# Core_Board.net
KiCad netlist of a schematic drawn in Altium Designer
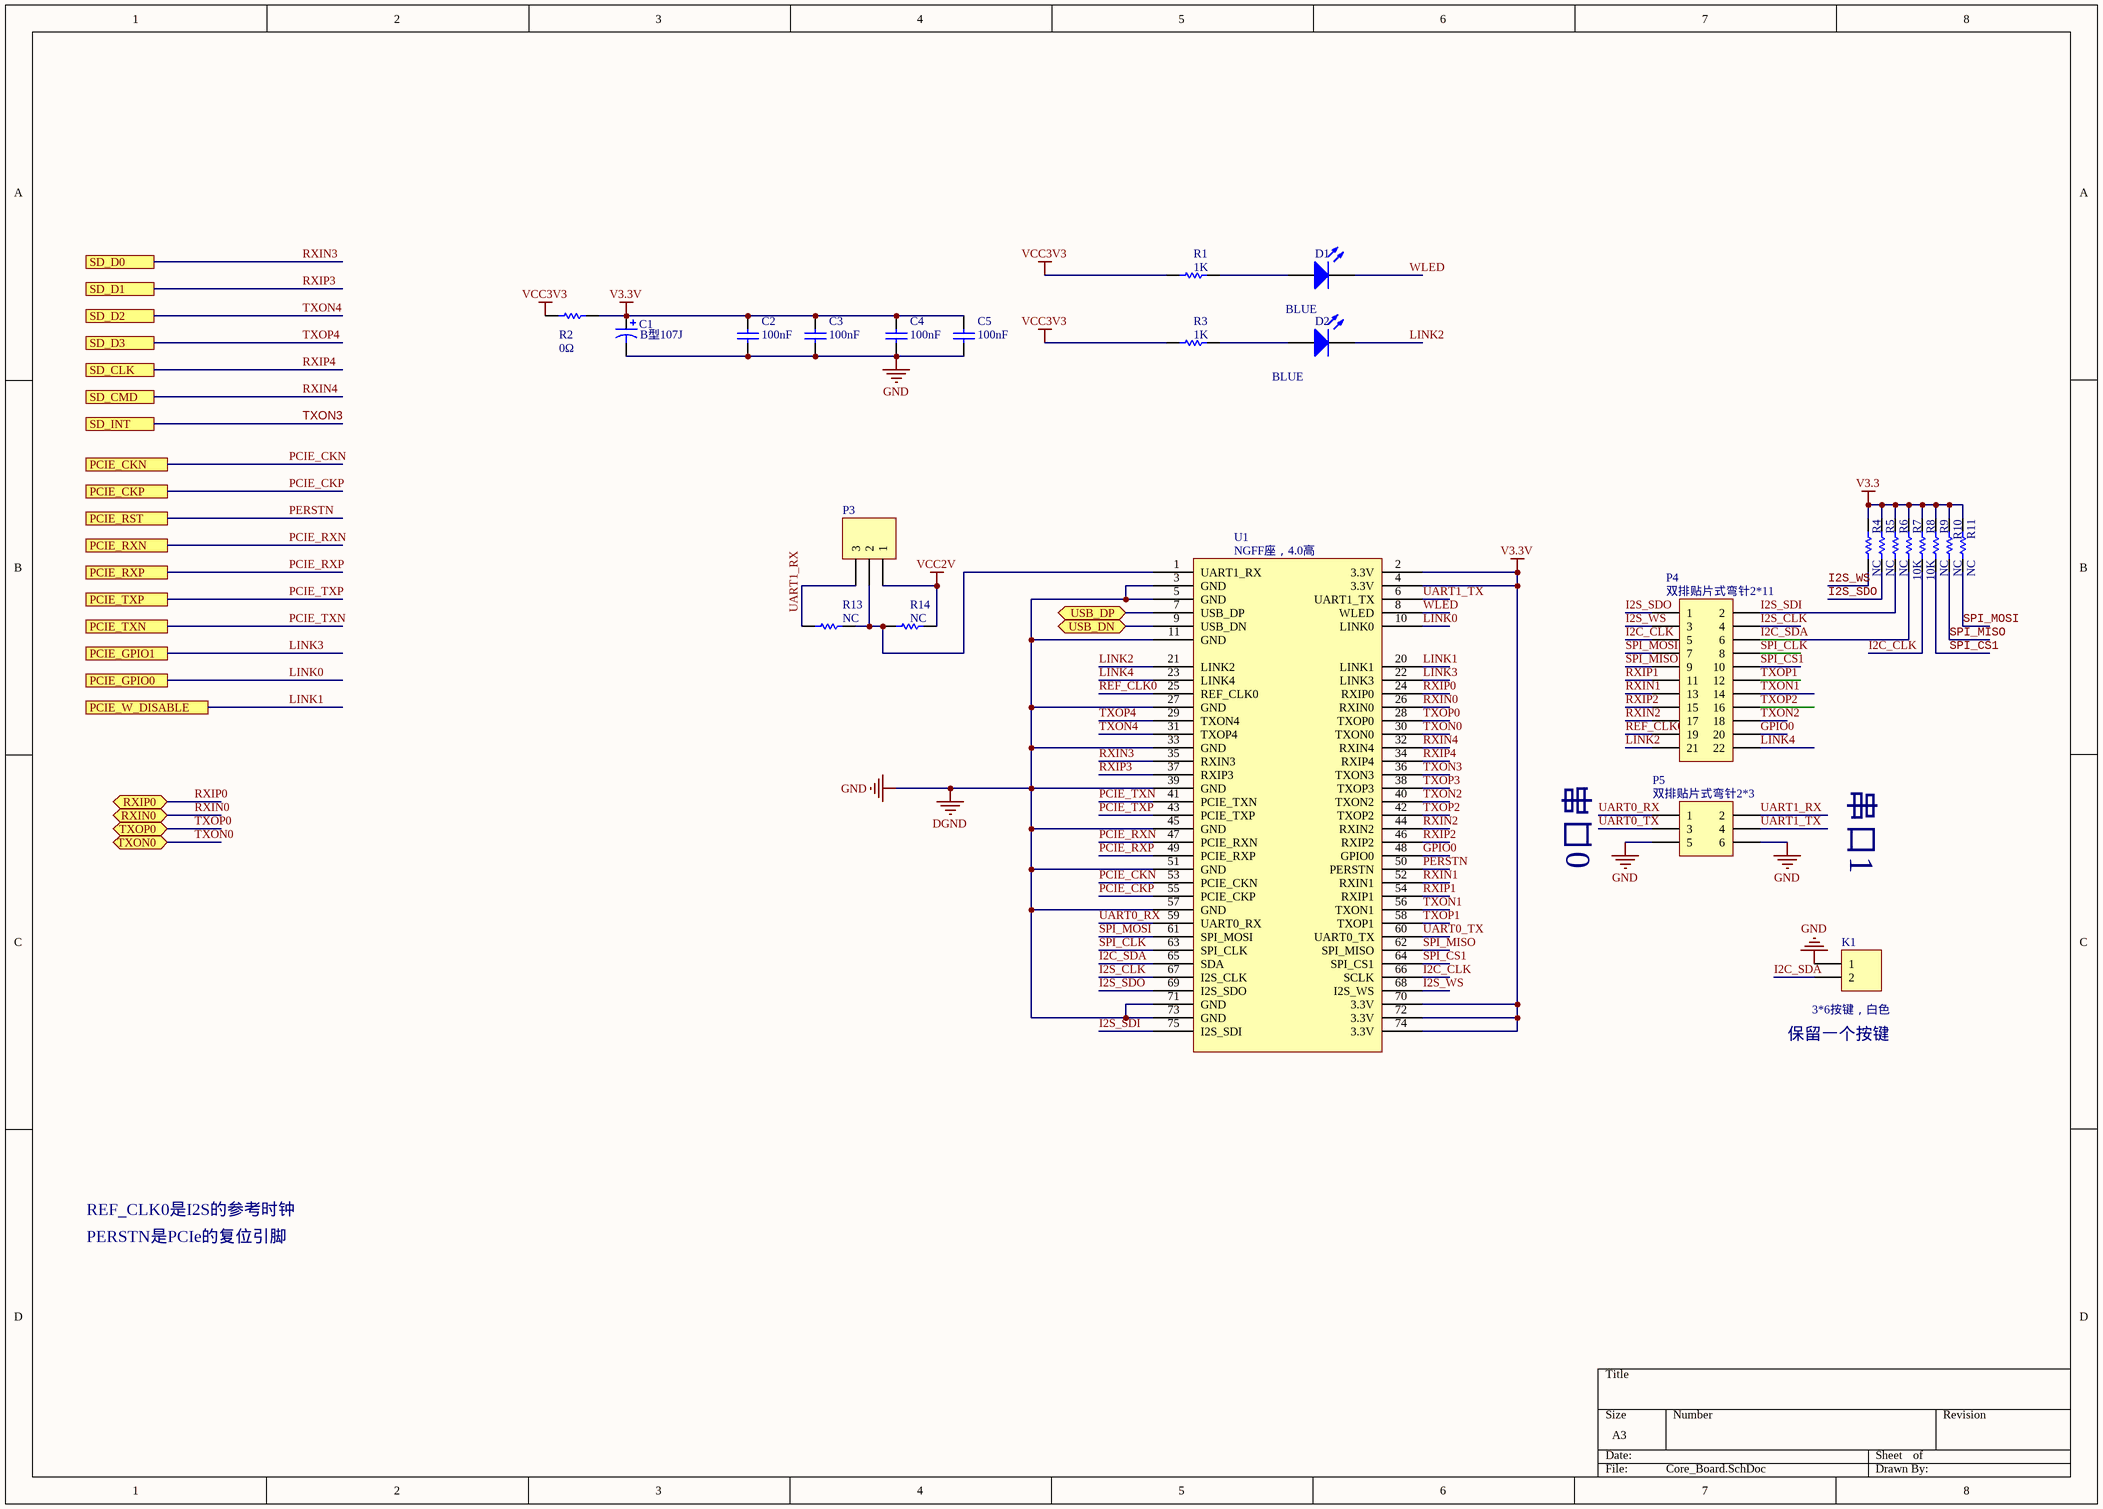
[diagram p0: Core_Board.SchDoc]

(export (version "E")
  (design (tool "Eeschema 10.0.6"))
  (components
    (comp (ref "C1")
      (value "B型107J")
      (footprint "C1210-A")
      (description "Polarized Capacitor (Radial)")
      (fields (field (name "PUBLISHER") "Altium Limited"))
      (libsource (lib "Miscellaneous Devices") (part "Cap Pol1"))
    )
    (comp (ref "C2")
      (value "100nF")
      (footprint "0402")
      (description "Capacitor")
      (fields (field (name "PUBLISHER") "Altium Limited"))
      (libsource (lib "Miscellaneous Devices") (part "Cap"))
    )
    (comp (ref "C3")
      (value "100nF")
      (footprint "0402")
      (description "Capacitor")
      (fields (field (name "PUBLISHER") "Altium Limited"))
      (libsource (lib "Miscellaneous Devices") (part "Cap"))
    )
    (comp (ref "C4")
      (value "100nF")
      (footprint "0402")
      (description "Capacitor")
      (fields (field (name "PUBLISHER") "Altium Limited"))
      (libsource (lib "Miscellaneous Devices") (part "Cap"))
    )
    (comp (ref "C5")
      (value "100nF")
      (footprint "0402")
      (description "Capacitor")
      (fields (field (name "PUBLISHER") "Altium Limited"))
      (libsource (lib "Miscellaneous Devices") (part "Cap"))
    )
    (comp (ref "D1")
      (value "BLUE")
      (footprint "LED0603")
      (description "LED")
      (libsource (lib "schumyhao's_Device") (part "LED"))
    )
    (comp (ref "D2")
      (value "BLUE")
      (footprint "LED0603")
      (description "LED")
      (libsource (lib "schumyhao's_Device") (part "LED"))
    )
    (comp (ref "K1")
      (value "3*6按键，白色")
      (footprint "3*6key")
      (description "Header, 2-Pin")
      (fields (field (name "PUBLISHER") "Altium Limited"))
      (libsource (lib "Miscellaneous Connectors") (part "Header 2"))
    )
    (comp (ref "P3")
      (value "3P单排针")
      (footprint "SIP3-2.54")
      (description "Header, 3-Pin")
      (fields (field (name "PUBLISHER") "Altium Limited"))
      (libsource (lib "Miscellaneous Connectors") (part "Header 3"))
    )
    (comp (ref "P4")
      (value "双排贴片式弯针2*11")
      (footprint "SIP2*11-2.54 PATCH")
      (description "Header, 11-Pin, Dual row")
      (fields (field (name "PUBLISHER") "Altium Limited"))
      (libsource (lib "Miscellaneous Connectors") (part "Header 11X2"))
    )
    (comp (ref "P5")
      (value "双排贴片式弯针2*3")
      (footprint "SIP2*3-2.54 PATCH")
      (description "Header, 3-Pin, Dual row")
      (fields (field (name "PUBLISHER") "Altium Limited"))
      (libsource (lib "Miscellaneous Connectors") (part "Header 3X2"))
    )
    (comp (ref "R1")
      (value "1K")
      (footprint "0402")
      (description "Semiconductor Resistor")
      (libsource (lib "schumyhao's_Device") (part "Res Semi"))
    )
    (comp (ref "R2")
      (value "0Ω")
      (footprint "R0805N")
      (description "Semiconductor Resistor")
      (fields (field (name "PUBLISHER") "Altium Limited"))
      (libsource (lib "Miscellaneous Devices") (part "Res Semi"))
    )
    (comp (ref "R3")
      (value "1K")
      (footprint "0402")
      (description "Semiconductor Resistor")
      (libsource (lib "schumyhao's_Device") (part "Res Semi"))
    )
    (comp (ref "R4")
      (value "NC")
      (footprint "0402")
      (description "Semiconductor Resistor")
      (libsource (lib "schumyhao's_Device") (part "Res Semi"))
    )
    (comp (ref "R5")
      (value "NC")
      (footprint "0402")
      (description "Semiconductor Resistor")
      (libsource (lib "schumyhao's_Device") (part "Res Semi"))
    )
    (comp (ref "R6")
      (value "NC")
      (footprint "0402")
      (description "Semiconductor Resistor")
      (libsource (lib "schumyhao's_Device") (part "Res Semi"))
    )
    (comp (ref "R7")
      (value "10K")
      (footprint "0402")
      (description "Semiconductor Resistor")
      (libsource (lib "schumyhao's_Device") (part "Res Semi"))
    )
    (comp (ref "R8")
      (value "10K")
      (footprint "0402")
      (description "Semiconductor Resistor")
      (libsource (lib "schumyhao's_Device") (part "Res Semi"))
    )
    (comp (ref "R9")
      (value "NC")
      (footprint "0402")
      (description "Semiconductor Resistor")
      (libsource (lib "schumyhao's_Device") (part "Res Semi"))
    )
    (comp (ref "R10")
      (value "NC")
      (footprint "0402")
      (description "Semiconductor Resistor")
      (libsource (lib "schumyhao's_Device") (part "Res Semi"))
    )
    (comp (ref "R11")
      (value "NC")
      (footprint "0402")
      (description "Semiconductor Resistor")
      (libsource (lib "schumyhao's_Device") (part "Res Semi"))
    )
    (comp (ref "R13")
      (value "NC")
      (footprint "0402")
      (description "Semiconductor Resistor")
      (fields (field (name "PUBLISHER") "Altium Limited"))
      (libsource (lib "Miscellaneous Devices") (part "Res Semi"))
    )
    (comp (ref "R14")
      (value "NC")
      (footprint "0402")
      (description "Semiconductor Resistor")
      (fields (field (name "PUBLISHER") "Altium Limited"))
      (libsource (lib "Miscellaneous Devices") (part "Res Semi"))
    )
    (comp (ref "U1") (value "NGFF座，4.0高") (footprint "NGFF M.2") (libsource (lib "IC_Sch_lib") (part "core")))
  )
  (nets
    (net (code "1") (name "/GPIO0") (class "Default")
      (node (ref "P4") (pin "20") (pinfunction "20_20") (pintype "passive"))
      (node (ref "U1") (pin "48") (pinfunction "GPIO0_48") (pintype "passive"))
    )
    (net (code "2") (name "/I2C_CLK") (class "Default")
      (node (ref "P4") (pin "5") (pinfunction "5_5") (pintype "passive"))
      (node (ref "R8") (pin "1") (pinfunction "1_1") (pintype "passive"))
      (node (ref "U1") (pin "66") (pinfunction "SCLK_66") (pintype "passive"))
    )
    (net (code "3") (name "/I2C_SDA") (class "Default")
      (node (ref "K1") (pin "2") (pinfunction "2_2") (pintype "passive"))
      (node (ref "P4") (pin "6") (pinfunction "6_6") (pintype "passive"))
      (node (ref "R7") (pin "1") (pinfunction "1_1") (pintype "passive"))
      (node (ref "U1") (pin "65") (pinfunction "SDA_65") (pintype "passive"))
    )
    (net (code "4") (name "/I2S_CLK") (class "Default")
      (node (ref "P4") (pin "4") (pinfunction "4_4") (pintype "passive"))
      (node (ref "U1") (pin "67") (pinfunction "I2S_CLK_67") (pintype "passive"))
    )
    (net (code "5") (name "/I2S_SDI") (class "Default")
      (node (ref "P4") (pin "2") (pinfunction "2_2") (pintype "passive"))
      (node (ref "R6") (pin "1") (pinfunction "1_1") (pintype "passive"))
      (node (ref "U1") (pin "75") (pinfunction "I2S_SDI_75") (pintype "passive"))
    )
    (net (code "6") (name "/I2S_SDO") (class "Default")
      (node (ref "P4") (pin "1") (pinfunction "1_1") (pintype "passive"))
      (node (ref "R5") (pin "1") (pinfunction "1_1") (pintype "passive"))
      (node (ref "U1") (pin "69") (pinfunction "I2S_SDO_69") (pintype "passive"))
    )
    (net (code "7") (name "/I2S_WS") (class "Default")
      (node (ref "P4") (pin "3") (pinfunction "3_3") (pintype "passive"))
      (node (ref "R4") (pin "1") (pinfunction "1_1") (pintype "passive"))
      (node (ref "U1") (pin "68") (pinfunction "I2S_WS_68") (pintype "passive"))
    )
    (net (code "8") (name "/LINK0") (class "Default")
      (node (ref "U1") (pin "10") (pinfunction "LINK0_10") (pintype "passive"))
    )
    (net (code "9") (name "/LINK1") (class "Default")
      (node (ref "U1") (pin "20") (pinfunction "LINK1_20") (pintype "passive"))
    )
    (net (code "10") (name "/LINK2") (class "Default")
      (node (ref "D2") (pin "2") (pinfunction "2_2") (pintype "passive"))
      (node (ref "P4") (pin "21") (pinfunction "21_21") (pintype "passive"))
      (node (ref "U1") (pin "21") (pinfunction "LINK2_21") (pintype "passive"))
    )
    (net (code "11") (name "/LINK3") (class "Default")
      (node (ref "U1") (pin "22") (pinfunction "LINK3_22") (pintype "passive"))
    )
    (net (code "12") (name "/LINK4") (class "Default")
      (node (ref "P4") (pin "22") (pinfunction "22_22") (pintype "passive"))
      (node (ref "U1") (pin "23") (pinfunction "LINK4_23") (pintype "passive"))
    )
    (net (code "13") (name "/PCIE_CKN") (class "Default")
      (node (ref "U1") (pin "53") (pinfunction "PCIE_CKN_53") (pintype "passive"))
    )
    (net (code "14") (name "/PCIE_CKP") (class "Default")
      (node (ref "U1") (pin "55") (pinfunction "PCIE_CKP_55") (pintype "passive"))
    )
    (net (code "15") (name "/PCIE_RXN") (class "Default")
      (node (ref "U1") (pin "47") (pinfunction "PCIE_RXN_47") (pintype "passive"))
    )
    (net (code "16") (name "/PCIE_RXP") (class "Default")
      (node (ref "U1") (pin "49") (pinfunction "PCIE_RXP_49") (pintype "passive"))
    )
    (net (code "17") (name "/PCIE_TXN") (class "Default")
      (node (ref "U1") (pin "41") (pinfunction "PCIE_TXN_41") (pintype "passive"))
    )
    (net (code "18") (name "/PCIE_TXP") (class "Default")
      (node (ref "U1") (pin "43") (pinfunction "PCIE_TXP_43") (pintype "passive"))
    )
    (net (code "19") (name "/PERSTN") (class "Default")
      (node (ref "U1") (pin "50") (pinfunction "PERSTN_50") (pintype "passive"))
    )
    (net (code "20") (name "/REF_CLK0") (class "Default")
      (node (ref "P4") (pin "19") (pinfunction "19_19") (pintype "passive"))
      (node (ref "U1") (pin "25") (pinfunction "REF_CLK0_25") (pintype "passive"))
    )
    (net (code "21") (name "/RXIN0") (class "Default")
      (node (ref "U1") (pin "26") (pinfunction "RXIN0_26") (pintype "passive"))
    )
    (net (code "22") (name "/RXIN1") (class "Default")
      (node (ref "P4") (pin "13") (pinfunction "13_13") (pintype "passive"))
      (node (ref "U1") (pin "52") (pinfunction "RXIN1_52") (pintype "passive"))
    )
    (net (code "23") (name "/RXIN2") (class "Default")
      (node (ref "P4") (pin "17") (pinfunction "17_17") (pintype "passive"))
      (node (ref "U1") (pin "44") (pinfunction "RXIN2_44") (pintype "passive"))
    )
    (net (code "24") (name "/RXIN3") (class "Default")
      (node (ref "U1") (pin "35") (pinfunction "RXIN3_35") (pintype "passive"))
    )
    (net (code "25") (name "/RXIN4") (class "Default")
      (node (ref "U1") (pin "32") (pinfunction "RXIN4_32") (pintype "passive"))
    )
    (net (code "26") (name "/RXIP0") (class "Default")
      (node (ref "U1") (pin "24") (pinfunction "RXIP0_24") (pintype "passive"))
    )
    (net (code "27") (name "/RXIP1") (class "Default")
      (node (ref "P4") (pin "11") (pinfunction "11_11") (pintype "passive"))
      (node (ref "U1") (pin "54") (pinfunction "RXIP1_54") (pintype "passive"))
    )
    (net (code "28") (name "/RXIP2") (class "Default")
      (node (ref "P4") (pin "15") (pinfunction "15_15") (pintype "passive"))
      (node (ref "U1") (pin "46") (pinfunction "RXIP2_46") (pintype "passive"))
    )
    (net (code "29") (name "/RXIP3") (class "Default")
      (node (ref "U1") (pin "37") (pinfunction "RXIP3_37") (pintype "passive"))
    )
    (net (code "30") (name "/RXIP4") (class "Default")
      (node (ref "U1") (pin "34") (pinfunction "RXIP4_34") (pintype "passive"))
    )
    (net (code "31") (name "/SPI_CLK") (class "Default")
      (node (ref "P4") (pin "8") (pinfunction "8_8") (pintype "passive"))
      (node (ref "U1") (pin "63") (pinfunction "SPI_CLK_63") (pintype "passive"))
    )
    (net (code "32") (name "/SPI_CS1") (class "Default")
      (node (ref "P4") (pin "10") (pinfunction "10_10") (pintype "passive"))
      (node (ref "R9") (pin "1") (pinfunction "1_1") (pintype "passive"))
      (node (ref "U1") (pin "64") (pinfunction "SPI_CS1_64") (pintype "passive"))
    )
    (net (code "33") (name "/SPI_MISO") (class "Default")
      (node (ref "P4") (pin "9") (pinfunction "9_9") (pintype "passive"))
      (node (ref "R10") (pin "1") (pinfunction "1_1") (pintype "passive"))
      (node (ref "U1") (pin "62") (pinfunction "SPI_MISO_62") (pintype "passive"))
    )
    (net (code "34") (name "/SPI_MOSI") (class "Default")
      (node (ref "P4") (pin "7") (pinfunction "7_7") (pintype "passive"))
      (node (ref "R11") (pin "1") (pinfunction "1_1") (pintype "passive"))
      (node (ref "U1") (pin "61") (pinfunction "SPI_MOSI_61") (pintype "passive"))
    )
    (net (code "35") (name "/TXON0") (class "Default")
      (node (ref "U1") (pin "30") (pinfunction "TXON0_30") (pintype "passive"))
    )
    (net (code "36") (name "/TXON1") (class "Default")
      (node (ref "P4") (pin "14") (pinfunction "14_14") (pintype "passive"))
      (node (ref "U1") (pin "56") (pinfunction "TXON1_56") (pintype "passive"))
    )
    (net (code "37") (name "/TXON2") (class "Default")
      (node (ref "P4") (pin "18") (pinfunction "18_18") (pintype "passive"))
      (node (ref "U1") (pin "40") (pinfunction "TXON2_40") (pintype "passive"))
    )
    (net (code "38") (name "/TXON3") (class "Default")
      (node (ref "U1") (pin "36") (pinfunction "TXON3_36") (pintype "passive"))
    )
    (net (code "39") (name "/TXON4") (class "Default")
      (node (ref "U1") (pin "31") (pinfunction "TXOP4_31") (pintype "passive"))
    )
    (net (code "40") (name "/TXOP0") (class "Default")
      (node (ref "U1") (pin "28") (pinfunction "TXOP0_28") (pintype "passive"))
    )
    (net (code "41") (name "/TXOP1") (class "Default")
      (node (ref "P4") (pin "12") (pinfunction "12_12") (pintype "passive"))
      (node (ref "U1") (pin "58") (pinfunction "TXOP1_58") (pintype "passive"))
    )
    (net (code "42") (name "/TXOP2") (class "Default")
      (node (ref "P4") (pin "16") (pinfunction "16_16") (pintype "passive"))
      (node (ref "U1") (pin "42") (pinfunction "TXOP2_42") (pintype "passive"))
    )
    (net (code "43") (name "/TXOP3") (class "Default")
      (node (ref "U1") (pin "38") (pinfunction "TXOP3_38") (pintype "passive"))
    )
    (net (code "44") (name "/TXOP4") (class "Default")
      (node (ref "U1") (pin "29") (pinfunction "TXON4_29") (pintype "passive"))
    )
    (net (code "45") (name "/UART0_RX") (class "Default")
      (node (ref "P5") (pin "1") (pinfunction "1_1") (pintype "passive"))
      (node (ref "U1") (pin "59") (pinfunction "UART0_RX_59") (pintype "passive"))
    )
    (net (code "46") (name "/UART0_TX") (class "Default")
      (node (ref "P5") (pin "3") (pinfunction "3_3") (pintype "passive"))
      (node (ref "U1") (pin "60") (pinfunction "UART0_TX_60") (pintype "passive"))
    )
    (net (code "47") (name "/UART1_RX") (class "Default")
      (node (ref "P3") (pin "3") (pinfunction "3_3") (pintype "passive"))
      (node (ref "P5") (pin "2") (pinfunction "2_2") (pintype "passive"))
      (node (ref "R13") (pin "1") (pinfunction "1_1") (pintype "passive"))
    )
    (net (code "48") (name "/UART1_TX") (class "Default")
      (node (ref "P5") (pin "4") (pinfunction "4_4") (pintype "passive"))
      (node (ref "U1") (pin "6") (pinfunction "UART1_TX_6") (pintype "passive"))
    )
    (net (code "49") (name "/USB_DN") (class "Default")
      (node (ref "U1") (pin "9") (pinfunction "USB_DN_9") (pintype "passive"))
    )
    (net (code "50") (name "/USB_DP") (class "Default")
      (node (ref "U1") (pin "7") (pinfunction "USB_DP_7") (pintype "passive"))
    )
    (net (code "51") (name "/WLED") (class "Default")
      (node (ref "D1") (pin "2") (pinfunction "2_2") (pintype "passive"))
      (node (ref "U1") (pin "8") (pinfunction "WLED_8") (pintype "passive"))
    )
    (net (code "52") (name "DGND") (class "Default")
      (node (ref "C1") (pin "2") (pinfunction "2_2") (pintype "passive"))
      (node (ref "C2") (pin "1") (pinfunction "1_1") (pintype "passive"))
      (node (ref "C3") (pin "1") (pinfunction "1_1") (pintype "passive"))
      (node (ref "C4") (pin "1") (pinfunction "1_1") (pintype "passive"))
      (node (ref "C5") (pin "1") (pinfunction "1_1") (pintype "passive"))
      (node (ref "K1") (pin "1") (pinfunction "1_1") (pintype "passive"))
      (node (ref "P5") (pin "5") (pinfunction "5_5") (pintype "passive"))
      (node (ref "P5") (pin "6") (pinfunction "6_6") (pintype "passive"))
      (node (ref "U1") (pin "11") (pinfunction "GND_11") (pintype "passive"))
      (node (ref "U1") (pin "27") (pinfunction "GND_27") (pintype "passive"))
      (node (ref "U1") (pin "3") (pinfunction "GND_3") (pintype "passive"))
      (node (ref "U1") (pin "33") (pinfunction "GND_33") (pintype "passive"))
      (node (ref "U1") (pin "39") (pinfunction "GND_39") (pintype "passive"))
      (node (ref "U1") (pin "45") (pinfunction "GND_45") (pintype "passive"))
      (node (ref "U1") (pin "5") (pinfunction "GND_5") (pintype "passive"))
      (node (ref "U1") (pin "51") (pinfunction "GND_51") (pintype "passive"))
      (node (ref "U1") (pin "57") (pinfunction "GND_57") (pintype "passive"))
      (node (ref "U1") (pin "71") (pinfunction "GND_71") (pintype "passive"))
      (node (ref "U1") (pin "73") (pinfunction "GND_73") (pintype "passive"))
    )
    (net (code "53") (name "Net-(D1-Pad1)") (class "Default")
      (node (ref "D1") (pin "1") (pinfunction "1_1") (pintype "passive"))
      (node (ref "R1") (pin "2") (pinfunction "2_2") (pintype "passive"))
    )
    (net (code "54") (name "Net-(D2-Pad1)") (class "Default")
      (node (ref "D2") (pin "1") (pinfunction "1_1") (pintype "passive"))
      (node (ref "R3") (pin "2") (pinfunction "2_2") (pintype "passive"))
    )
    (net (code "55") (name "Net-(U1-UART1_RX)") (class "Default")
      (node (ref "P3") (pin "2") (pinfunction "2_2") (pintype "passive"))
      (node (ref "R13") (pin "2") (pinfunction "2_2") (pintype "passive"))
      (node (ref "R14") (pin "1") (pinfunction "1_1") (pintype "passive"))
      (node (ref "U1") (pin "1") (pinfunction "UART1_RX_1") (pintype "passive"))
    )
    (net (code "56") (name "V3.3") (class "Default")
      (node (ref "R10") (pin "2") (pinfunction "2_2") (pintype "passive"))
      (node (ref "R11") (pin "2") (pinfunction "2_2") (pintype "passive"))
      (node (ref "R4") (pin "2") (pinfunction "2_2") (pintype "passive"))
      (node (ref "R5") (pin "2") (pinfunction "2_2") (pintype "passive"))
      (node (ref "R6") (pin "2") (pinfunction "2_2") (pintype "passive"))
      (node (ref "R7") (pin "2") (pinfunction "2_2") (pintype "passive"))
      (node (ref "R8") (pin "2") (pinfunction "2_2") (pintype "passive"))
      (node (ref "R9") (pin "2") (pinfunction "2_2") (pintype "passive"))
    )
    (net (code "57") (name "V3.3V") (class "Default")
      (node (ref "C1") (pin "1") (pinfunction "1_1") (pintype "passive"))
      (node (ref "C2") (pin "2") (pinfunction "2_2") (pintype "passive"))
      (node (ref "C3") (pin "2") (pinfunction "2_2") (pintype "passive"))
      (node (ref "C4") (pin "2") (pinfunction "2_2") (pintype "passive"))
      (node (ref "C5") (pin "2") (pinfunction "2_2") (pintype "passive"))
      (node (ref "R2") (pin "2") (pinfunction "2_2") (pintype "passive"))
      (node (ref "U1") (pin "2") (pinfunction "3.3V_2") (pintype "passive"))
      (node (ref "U1") (pin "4") (pinfunction "3.3V_4") (pintype "passive"))
      (node (ref "U1") (pin "70") (pinfunction "3.3V_70") (pintype "passive"))
      (node (ref "U1") (pin "72") (pinfunction "3.3V_72") (pintype "passive"))
      (node (ref "U1") (pin "74") (pinfunction "3.3V_74") (pintype "passive"))
    )
    (net (code "58") (name "VCC2V") (class "Default")
      (node (ref "P3") (pin "1") (pinfunction "1_1") (pintype "passive"))
      (node (ref "R14") (pin "2") (pinfunction "2_2") (pintype "passive"))
    )
    (net (code "59") (name "VCC3V3") (class "Default")
      (node (ref "R1") (pin "1") (pinfunction "1_1") (pintype "passive"))
      (node (ref "R2") (pin "1") (pinfunction "1_1") (pintype "passive"))
      (node (ref "R3") (pin "1") (pinfunction "1_1") (pintype "passive"))
    )
  )
)
